# powercontrol.net
KiCad netlist of a schematic drawn in EAGLE
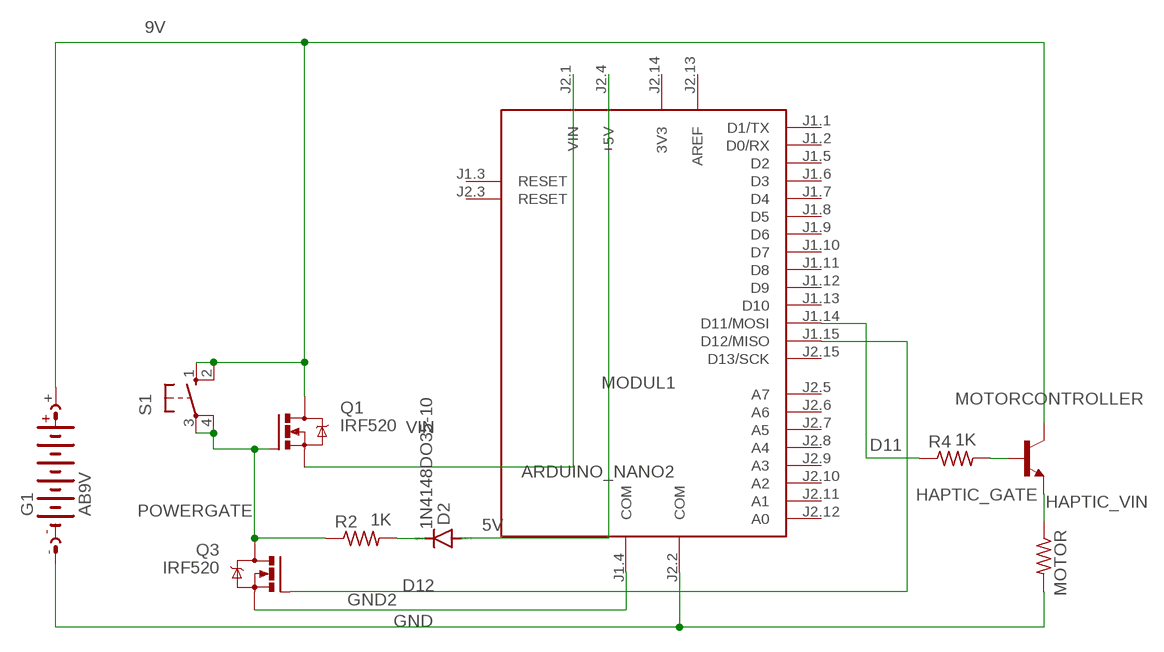
[diagram p0: schematic, sheet 1]

(export (version "E")
  (design (tool "Eeschema 10.0.6"))
  (components
    (comp (ref "D2")
      (value "1N4148DO35-10")
      (footprint "eagle-import:DO35-10")
      (libsource (lib "eagle-import") (part "1N4148DO35-10"))
    )
    (comp (ref "G1")
      (value "AB9V")
      (footprint "eagle-import:AB9V")
      (libsource (lib "eagle-import") (part "AB9V"))
    )
    (comp (ref "MODUL1")
      (value "ARDUINO_NANO2")
      (footprint "eagle-import:ARDUINO_NANO2")
      (libsource (lib "eagle-import") (part "ARDUINO_NANO2"))
    )
    (comp (ref "MOTOR")
      (value "1K")
      (footprint "eagle-import:0204_7")
      (libsource (lib "eagle-import") (part "R-US_0204/7"))
    )
    (comp (ref "MOTORCONTROLLER")
      (value "2N2222-NPN-TO92-EBC")
      (footprint "eagle-import:TO92-EBC")
      (libsource (lib "eagle-import") (part "-NPN-TO92-EBC2N2222"))
    )
    (comp (ref "Q1")
      (value "IRF520")
      (footprint "eagle-import:TO220BV")
      (libsource (lib "eagle-import") (part "IRF520"))
    )
    (comp (ref "Q3")
      (value "IRF520")
      (footprint "eagle-import:TO220BV")
      (libsource (lib "eagle-import") (part "IRF520"))
    )
    (comp (ref "R2")
      (value "1K")
      (footprint "eagle-import:0204_7")
      (libsource (lib "eagle-import") (part "R-US_0204/7"))
    )
    (comp (ref "R4")
      (value "1K")
      (footprint "eagle-import:0204_7")
      (libsource (lib "eagle-import") (part "R-US_0204/7"))
    )
    (comp (ref "S1")
      (value "10-XX")
      (footprint "eagle-import:B3F-10XX")
      (fields (field (name "MPN") "B3F-1000"))
      (libsource (lib "eagle-import") (part "10-XX"))
    )
  )
  (nets
    (net (code "1") (name "/3V3") (class "Default")
      (node (ref "MODUL1") (pin "J2.14") (pinfunction "3V3_J2.14") (pintype "power_in"))
    )
    (net (code "2") (name "/5V") (class "Default")
      (node (ref "D2") (pin "A") (pinfunction "A_A") (pintype "passive"))
      (node (ref "MODUL1") (pin "J2.4") (pinfunction "+5V_J2.4") (pintype "power_in"))
    )
    (net (code "3") (name "/9V") (class "Default")
      (node (ref "G1") (pin "+") (pinfunction "+_+") (pintype "passive"))
      (node (ref "MOTORCONTROLLER") (pin "C") (pinfunction "C_C") (pintype "passive"))
      (node (ref "Q1") (pin "D") (pinfunction "D_D") (pintype "passive"))
      (node (ref "S1") (pin "1") (pinfunction "S_1") (pintype "passive"))
      (node (ref "S1") (pin "2") (pinfunction "S1_2") (pintype "passive"))
    )
    (net (code "4") (name "/AREF") (class "Default")
      (node (ref "MODUL1") (pin "J2.13") (pinfunction "AREF_J2.13") (pintype "power_in"))
    )
    (net (code "5") (name "/D11") (class "Default")
      (node (ref "MODUL1") (pin "J1.14") (pinfunction "D11/MOSI_J1.14") (pintype "bidirectional"))
      (node (ref "R4") (pin "1") (pinfunction "1_1") (pintype "passive"))
    )
    (net (code "6") (name "/D12") (class "Default")
      (node (ref "MODUL1") (pin "J1.15") (pinfunction "D12/MISO_J1.15") (pintype "bidirectional"))
      (node (ref "Q3") (pin "G") (pinfunction "G_G") (pintype "passive"))
    )
    (net (code "7") (name "/GND") (class "Default")
      (node (ref "G1") (pin "-") (pinfunction "-_-") (pintype "passive"))
      (node (ref "MODUL1") (pin "J2.2") (pinfunction "COM_J2.2") (pintype "power_in"))
      (node (ref "MOTOR") (pin "2") (pinfunction "2_2") (pintype "passive"))
    )
    (net (code "8") (name "/GND2") (class "Default")
      (node (ref "MODUL1") (pin "J1.4") (pinfunction "COM_J1.4") (pintype "power_in"))
      (node (ref "Q3") (pin "S") (pinfunction "S_S") (pintype "passive"))
    )
    (net (code "9") (name "/HAPTIC_GATE") (class "Default")
      (node (ref "MOTORCONTROLLER") (pin "B") (pinfunction "B_B") (pintype "passive"))
      (node (ref "R4") (pin "2") (pinfunction "2_2") (pintype "passive"))
    )
    (net (code "10") (name "/HAPTIC_VIN") (class "Default")
      (node (ref "MOTOR") (pin "1") (pinfunction "1_1") (pintype "passive"))
      (node (ref "MOTORCONTROLLER") (pin "E") (pinfunction "E_E") (pintype "passive"))
    )
    (net (code "11") (name "/POWERGATE") (class "Default")
      (node (ref "Q1") (pin "G") (pinfunction "G_G") (pintype "passive"))
      (node (ref "Q3") (pin "D") (pinfunction "D_D") (pintype "passive"))
      (node (ref "R2") (pin "1") (pinfunction "1_1") (pintype "passive"))
      (node (ref "S1") (pin "3") (pinfunction "P_3") (pintype "passive"))
      (node (ref "S1") (pin "4") (pinfunction "P1_4") (pintype "passive"))
    )
    (net (code "12") (name "/VIN") (class "Default")
      (node (ref "MODUL1") (pin "J2.1") (pinfunction "VIN_J2.1") (pintype "power_in"))
      (node (ref "Q1") (pin "S") (pinfunction "S_S") (pintype "passive"))
    )
    (net (code "13") (name "Net-(D2-PadC)") (class "Default")
      (node (ref "D2") (pin "C") (pinfunction "C_C") (pintype "passive"))
      (node (ref "R2") (pin "2") (pinfunction "2_2") (pintype "passive"))
    )
    (net (code "14") (name "unconnected-(MODUL1-A0-PadJ2.12)") (class "Default")
      (node (ref "MODUL1") (pin "J2.12") (pinfunction "A0_J2.12") (pintype "bidirectional"))
    )
    (net (code "15") (name "unconnected-(MODUL1-A1-PadJ2.11)") (class "Default")
      (node (ref "MODUL1") (pin "J2.11") (pinfunction "A1_J2.11") (pintype "bidirectional"))
    )
    (net (code "16") (name "unconnected-(MODUL1-A2-PadJ2.10)") (class "Default")
      (node (ref "MODUL1") (pin "J2.10") (pinfunction "A2_J2.10") (pintype "bidirectional"))
    )
    (net (code "17") (name "unconnected-(MODUL1-A3-PadJ2.9)") (class "Default")
      (node (ref "MODUL1") (pin "J2.9") (pinfunction "A3_J2.9") (pintype "bidirectional"))
    )
    (net (code "18") (name "unconnected-(MODUL1-A4-PadJ2.8)") (class "Default")
      (node (ref "MODUL1") (pin "J2.8") (pinfunction "A4_J2.8") (pintype "bidirectional"))
    )
    (net (code "19") (name "unconnected-(MODUL1-A5-PadJ2.7)") (class "Default")
      (node (ref "MODUL1") (pin "J2.7") (pinfunction "A5_J2.7") (pintype "bidirectional"))
    )
    (net (code "20") (name "unconnected-(MODUL1-A6-PadJ2.6)") (class "Default")
      (node (ref "MODUL1") (pin "J2.6") (pinfunction "A6_J2.6") (pintype "bidirectional"))
    )
    (net (code "21") (name "unconnected-(MODUL1-A7-PadJ2.5)") (class "Default")
      (node (ref "MODUL1") (pin "J2.5") (pinfunction "A7_J2.5") (pintype "bidirectional"))
    )
    (net (code "22") (name "unconnected-(MODUL1-D0{slash}RX-PadJ1.2)") (class "Default")
      (node (ref "MODUL1") (pin "J1.2") (pinfunction "D0/RX_J1.2") (pintype "bidirectional"))
    )
    (net (code "23") (name "unconnected-(MODUL1-D1{slash}TX-PadJ1.1)") (class "Default")
      (node (ref "MODUL1") (pin "J1.1") (pinfunction "D1/TX_J1.1") (pintype "bidirectional"))
    )
    (net (code "24") (name "unconnected-(MODUL1-D2-PadJ1.5)") (class "Default")
      (node (ref "MODUL1") (pin "J1.5") (pinfunction "D2_J1.5") (pintype "bidirectional"))
    )
    (net (code "25") (name "unconnected-(MODUL1-D3-PadJ1.6)") (class "Default")
      (node (ref "MODUL1") (pin "J1.6") (pinfunction "D3_J1.6") (pintype "bidirectional"))
    )
    (net (code "26") (name "unconnected-(MODUL1-D4-PadJ1.7)") (class "Default")
      (node (ref "MODUL1") (pin "J1.7") (pinfunction "D4_J1.7") (pintype "bidirectional"))
    )
    (net (code "27") (name "unconnected-(MODUL1-D5-PadJ1.8)") (class "Default")
      (node (ref "MODUL1") (pin "J1.8") (pinfunction "D5_J1.8") (pintype "bidirectional"))
    )
    (net (code "28") (name "unconnected-(MODUL1-D6-PadJ1.9)") (class "Default")
      (node (ref "MODUL1") (pin "J1.9") (pinfunction "D6_J1.9") (pintype "bidirectional"))
    )
    (net (code "29") (name "unconnected-(MODUL1-D7-PadJ1.10)") (class "Default")
      (node (ref "MODUL1") (pin "J1.10") (pinfunction "D7_J1.10") (pintype "bidirectional"))
    )
    (net (code "30") (name "unconnected-(MODUL1-D8-PadJ1.11)") (class "Default")
      (node (ref "MODUL1") (pin "J1.11") (pinfunction "D8_J1.11") (pintype "bidirectional"))
    )
    (net (code "31") (name "unconnected-(MODUL1-D9-PadJ1.12)") (class "Default")
      (node (ref "MODUL1") (pin "J1.12") (pinfunction "D9_J1.12") (pintype "bidirectional"))
    )
    (net (code "32") (name "unconnected-(MODUL1-D10-PadJ1.13)") (class "Default")
      (node (ref "MODUL1") (pin "J1.13") (pinfunction "D10_J1.13") (pintype "bidirectional"))
    )
    (net (code "33") (name "unconnected-(MODUL1-D13{slash}SCK-PadJ2.15)") (class "Default")
      (node (ref "MODUL1") (pin "J2.15") (pinfunction "D13/SCK_J2.15") (pintype "bidirectional"))
    )
    (net (code "34") (name "unconnected-(MODUL1-RESET-PadJ1.3)") (class "Default")
      (node (ref "MODUL1") (pin "J1.3") (pinfunction "RESET_J1.3") (pintype "bidirectional"))
    )
    (net (code "35") (name "unconnected-(MODUL1-RESET-PadJ2.3)") (class "Default")
      (node (ref "MODUL1") (pin "J2.3") (pinfunction "RESET_J2.3") (pintype "bidirectional"))
    )
  )
)
